# roboproj_q4.net
KiCad netlist of a schematic drawn in EAGLE
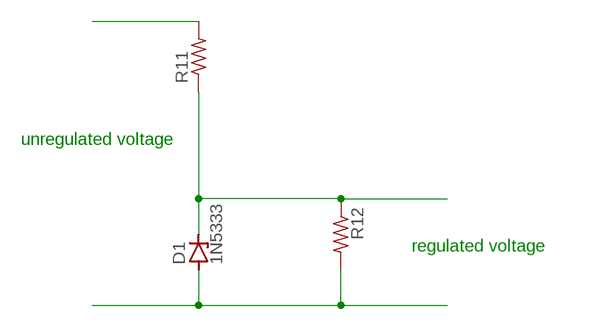
[diagram p0: schematic, sheet 1]

(export (version "E")
  (design (tool "Eeschema 10.0.6"))
  (components
    (comp (ref "D1")
      (value "1N5333")
      (footprint "eagle-import:C1702-15")
      (libsource (lib "eagle-import") (part "1N5333"))
    )
    (comp (ref "R11")
      (value "R-US_R0805")
      (footprint "eagle-import:R0805")
      (libsource (lib "eagle-import") (part "R-US_R0805"))
    )
    (comp (ref "R12")
      (value "R-US_R0805")
      (footprint "eagle-import:R0805")
      (libsource (lib "eagle-import") (part "R-US_R0805"))
    )
  )
  (nets
    (net (code "1") (name "Net-(D1-PadA)") (class "Default")
      (node (ref "D1") (pin "A") (pinfunction "A_A") (pintype "passive"))
      (node (ref "R12") (pin "2") (pinfunction "2_2") (pintype "passive"))
    )
    (net (code "2") (name "Net-(D1-PadC)") (class "Default")
      (node (ref "D1") (pin "C") (pinfunction "C_C") (pintype "passive"))
      (node (ref "R11") (pin "1") (pinfunction "1_1") (pintype "passive"))
      (node (ref "R12") (pin "1") (pinfunction "1_1") (pintype "passive"))
    )
    (net (code "3") (name "unconnected-(R11-Pad2)") (class "Default")
      (node (ref "R11") (pin "2") (pinfunction "2_2") (pintype "passive"))
    )
  )
)
